# usbtin.net
KiCad netlist of a schematic drawn in EAGLE
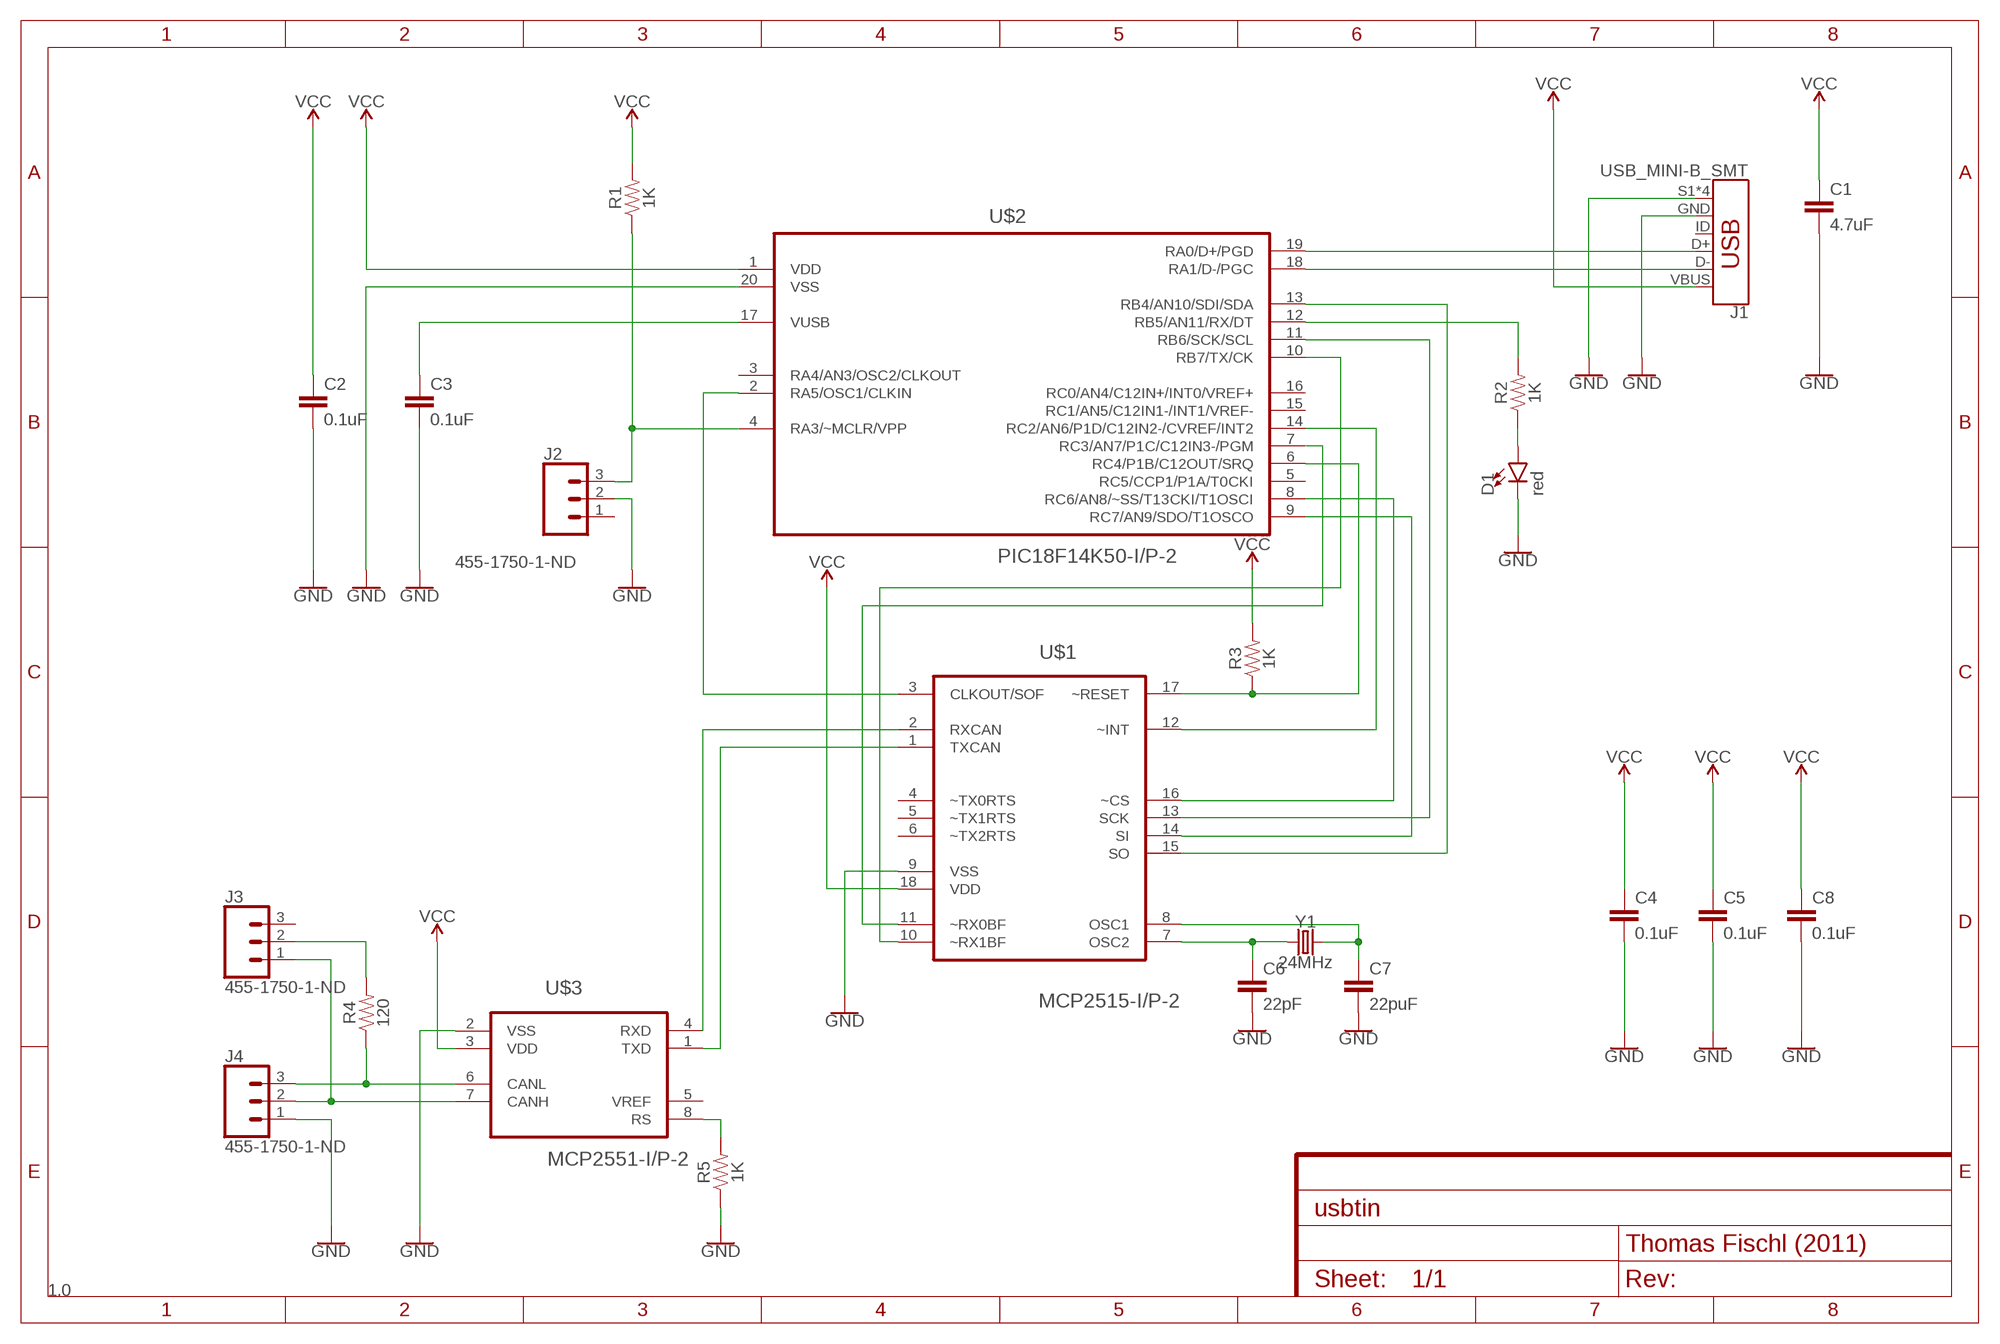
[diagram p0: schematic, sheet 1]

(export (version "E")
  (design (tool "Eeschema 10.0.6"))
  (components
    (comp (ref "C1")
      (value "4.7uF")
      (footprint "eagle-import:1206")
      (libsource (lib "eagle-import") (part "4.7UF-1206-16V-(+80/-20%)"))
    )
    (comp (ref "C2")
      (value "0.1uF")
      (footprint "eagle-import:0603")
      (libsource (lib "eagle-import") (part "0.1UF-0603-25V-5%"))
    )
    (comp (ref "C3")
      (value "0.1uF")
      (footprint "eagle-import:0603")
      (libsource (lib "eagle-import") (part "0.1UF-0603-25V-5%"))
    )
    (comp (ref "C4")
      (value "0.1uF")
      (footprint "eagle-import:0603")
      (libsource (lib "eagle-import") (part "0.1UF-0603-25V-5%"))
    )
    (comp (ref "C5")
      (value "0.1uF")
      (footprint "eagle-import:0603")
      (libsource (lib "eagle-import") (part "0.1UF-0603-25V-5%"))
    )
    (comp (ref "C6")
      (value "22pF")
      (footprint "eagle-import:0805")
      (libsource (lib "eagle-import") (part "1.0UF-0805-25V-10%"))
    )
    (comp (ref "C7")
      (value "22puF")
      (footprint "eagle-import:0805")
      (libsource (lib "eagle-import") (part "1.0UF-0805-25V-10%"))
    )
    (comp (ref "C8")
      (value "0.1uF")
      (footprint "eagle-import:0603")
      (libsource (lib "eagle-import") (part "0.1UF-0603-25V-5%"))
    )
    (comp (ref "D1")
      (value "red")
      (footprint "eagle-import:LED-1206")
      (libsource (lib "eagle-import") (part "LED1206"))
    )
    (comp (ref "J1")
      (value "USB_MINI-B_SMT")
      (footprint "eagle-import:USB-MINIB")
      (libsource (lib "eagle-import") (part "USB_MINI-B_SMT"))
    )
    (comp (ref "J2")
      (value "455-1750-1-ND")
      (footprint "eagle-import:1X03")
      (libsource (lib "eagle-import") (part "CONN_03"))
    )
    (comp (ref "J3")
      (value "455-1750-1-ND")
      (footprint "eagle-import:1X03")
      (libsource (lib "eagle-import") (part "CONN_03"))
    )
    (comp (ref "J4")
      (value "455-1750-1-ND")
      (footprint "eagle-import:1X03")
      (libsource (lib "eagle-import") (part "CONN_03"))
    )
    (comp (ref "R1")
      (value "1K")
      (footprint "eagle-import:0805")
      (libsource (lib "eagle-import") (part "0.3OHM-0805-1/8W-1%"))
    )
    (comp (ref "R2")
      (value "1K")
      (footprint "eagle-import:0805")
      (libsource (lib "eagle-import") (part "0.3OHM-0805-1/8W-1%"))
    )
    (comp (ref "R3")
      (value "1K")
      (footprint "eagle-import:0805")
      (libsource (lib "eagle-import") (part "0.3OHM-0805-1/8W-1%"))
    )
    (comp (ref "R4")
      (value "120")
      (footprint "eagle-import:0805")
      (libsource (lib "eagle-import") (part "0.3OHM-0805-1/8W-1%"))
    )
    (comp (ref "R5")
      (value "1K")
      (footprint "eagle-import:0805")
      (libsource (lib "eagle-import") (part "0.3OHM-0805-1/8W-1%"))
    )
    (comp (ref "U$1")
      (value "MCP2515-I/P-2")
      (footprint "eagle-import:DIP254P762X432-18")
      (fields (field (name "MPN") "MCP2515-I/P"))
      (libsource (lib "eagle-import") (part "MCP2515-I/P-2"))
    )
    (comp (ref "U$2")
      (value "PIC18F14K50-I/P-2")
      (footprint "eagle-import:DIP254P762X533-20")
      (fields (field (name "MPN") "PIC18F14K50-I/P"))
      (libsource (lib "eagle-import") (part "PIC18F14K50-I/P-2"))
    )
    (comp (ref "U$3")
      (value "MCP2551-I/P-2")
      (footprint "eagle-import:DIP254P762X432-8")
      (fields (field (name "MPN") "MCP2551-I/P"))
      (libsource (lib "eagle-import") (part "MCP2551-I/P-2"))
    )
    (comp (ref "Y1")
      (value "24MHz")
      (footprint "eagle-import:HC49US")
      (libsource (lib "eagle-import") (part "CRYSTALPTH-HC49US"))
    )
  )
  (nets
    (net (code "1") (name "GND") (class "Default")
      (node (ref "C1") (pin "2") (pinfunction "2_2") (pintype "passive"))
      (node (ref "C2") (pin "2") (pinfunction "2_2") (pintype "passive"))
      (node (ref "C3") (pin "2") (pinfunction "2_2") (pintype "passive"))
      (node (ref "C4") (pin "2") (pinfunction "2_2") (pintype "passive"))
      (node (ref "C5") (pin "2") (pinfunction "2_2") (pintype "passive"))
      (node (ref "C6") (pin "2") (pinfunction "2_2") (pintype "passive"))
      (node (ref "C7") (pin "2") (pinfunction "2_2") (pintype "passive"))
      (node (ref "C8") (pin "2") (pinfunction "2_2") (pintype "passive"))
      (node (ref "D1") (pin "C") (pinfunction "C_C") (pintype "passive"))
      (node (ref "J1") (pin "GND") (pinfunction "GND_GND") (pintype "power_in"))
      (node (ref "J1") (pin "S1") (pinfunction "SHIELD_S1") (pintype "bidirectional"))
      (node (ref "J1") (pin "S2") (pinfunction "SHIELD_S2") (pintype "bidirectional"))
      (node (ref "J1") (pin "S3") (pinfunction "SHIELD_S3") (pintype "bidirectional"))
      (node (ref "J1") (pin "S4") (pinfunction "SHIELD_S4") (pintype "bidirectional"))
      (node (ref "J2") (pin "2") (pinfunction "2_2") (pintype "passive"))
      (node (ref "J4") (pin "1") (pinfunction "1_1") (pintype "passive"))
      (node (ref "R5") (pin "1") (pinfunction "1_1") (pintype "passive"))
      (node (ref "U$1") (pin "9") (pinfunction "VSS_9") (pintype "power_in"))
      (node (ref "U$2") (pin "20") (pinfunction "VSS_20") (pintype "power_in"))
      (node (ref "U$3") (pin "2") (pinfunction "VSS_2") (pintype "power_in"))
    )
    (net (code "2") (name "Net-(D1-PadA)") (class "Default")
      (node (ref "D1") (pin "A") (pinfunction "A_A") (pintype "passive"))
      (node (ref "R2") (pin "1") (pinfunction "1_1") (pintype "passive"))
    )
    (net (code "3") (name "Net-(J3-Pad2)") (class "Default")
      (node (ref "J3") (pin "2") (pinfunction "2_2") (pintype "passive"))
      (node (ref "R4") (pin "2") (pinfunction "2_2") (pintype "passive"))
    )
    (net (code "4") (name "Net-(U$1-CLKOUT{slash}SOF)") (class "Default")
      (node (ref "U$1") (pin "3") (pinfunction "CLKOUT/SOF_3") (pintype "output"))
      (node (ref "U$2") (pin "2") (pinfunction "RA5/OSC1/CLKIN_2") (pintype "bidirectional"))
    )
    (net (code "5") (name "Net-(U$1-OSC1)") (class "Default")
      (node (ref "C7") (pin "1") (pinfunction "1_1") (pintype "passive"))
      (node (ref "U$1") (pin "8") (pinfunction "OSC1_8") (pintype "output"))
      (node (ref "Y1") (pin "2") (pinfunction "2_2") (pintype "passive"))
    )
    (net (code "6") (name "Net-(U$1-OSC2)") (class "Default")
      (node (ref "C6") (pin "1") (pinfunction "1_1") (pintype "passive"))
      (node (ref "U$1") (pin "7") (pinfunction "OSC2_7") (pintype "output"))
      (node (ref "Y1") (pin "1") (pinfunction "1_1") (pintype "passive"))
    )
    (net (code "7") (name "Net-(U$1-RXCAN)") (class "Default")
      (node (ref "U$1") (pin "2") (pinfunction "RXCAN_2") (pintype "input"))
      (node (ref "U$3") (pin "4") (pinfunction "RXD_4") (pintype "output"))
    )
    (net (code "8") (name "Net-(U$1-SCK)") (class "Default")
      (node (ref "U$1") (pin "13") (pinfunction "SCK_13") (pintype "input"))
      (node (ref "U$2") (pin "11") (pinfunction "RB6/SCK/SCL_11") (pintype "bidirectional"))
    )
    (net (code "9") (name "Net-(U$1-SI)") (class "Default")
      (node (ref "U$1") (pin "14") (pinfunction "SI_14") (pintype "input"))
      (node (ref "U$2") (pin "9") (pinfunction "RC7/AN9/SDO/T1OSCO_9") (pintype "bidirectional"))
    )
    (net (code "10") (name "Net-(U$1-SO)") (class "Default")
      (node (ref "U$1") (pin "15") (pinfunction "SO_15") (pintype "output"))
      (node (ref "U$2") (pin "13") (pinfunction "RB4/AN10/SDI/SDA_13") (pintype "bidirectional"))
    )
    (net (code "11") (name "Net-(U$1-TXCAN)") (class "Default")
      (node (ref "U$1") (pin "1") (pinfunction "TXCAN_1") (pintype "output"))
      (node (ref "U$3") (pin "1") (pinfunction "TXD_1") (pintype "input"))
    )
    (net (code "12") (name "Net-(U$1-~{CS})") (class "Default")
      (node (ref "U$1") (pin "16") (pinfunction "~{CS}_16") (pintype "input"))
      (node (ref "U$2") (pin "8") (pinfunction "RC6/AN8/~{SS/T13CKI/T1OSCI}_8") (pintype "bidirectional"))
    )
    (net (code "13") (name "Net-(U$1-~{INT})") (class "Default")
      (node (ref "U$1") (pin "12") (pinfunction "~{INT}_12") (pintype "output"))
      (node (ref "U$2") (pin "14") (pinfunction "RC2/AN6/P1D/C12IN2-/CVREF/INT2_14") (pintype "bidirectional"))
    )
    (net (code "14") (name "Net-(U$1-~{RESET})") (class "Default")
      (node (ref "R3") (pin "1") (pinfunction "1_1") (pintype "passive"))
      (node (ref "U$1") (pin "17") (pinfunction "~{RESET}_17") (pintype "input"))
      (node (ref "U$2") (pin "6") (pinfunction "RC4/P1B/C12OUT/SRQ_6") (pintype "bidirectional"))
    )
    (net (code "15") (name "Net-(U$1-~{RX0BF})") (class "Default")
      (node (ref "U$1") (pin "11") (pinfunction "~{RX0BF}_11") (pintype "output"))
      (node (ref "U$2") (pin "7") (pinfunction "RC3/AN7/P1C/C12IN3-/PGM_7") (pintype "bidirectional"))
    )
    (net (code "16") (name "Net-(U$1-~{RX1BF})") (class "Default")
      (node (ref "U$1") (pin "10") (pinfunction "~{RX1BF}_10") (pintype "output"))
      (node (ref "U$2") (pin "10") (pinfunction "RB7/TX/CK_10") (pintype "bidirectional"))
    )
    (net (code "17") (name "Net-(U$2-RA0{slash}D+{slash}PGD)") (class "Default")
      (node (ref "J1") (pin "D+") (pinfunction "D+_D+") (pintype "bidirectional"))
      (node (ref "U$2") (pin "19") (pinfunction "RA0/D+/PGD_19") (pintype "bidirectional"))
    )
    (net (code "18") (name "Net-(U$2-RA1{slash}D-{slash}PGC)") (class "Default")
      (node (ref "J1") (pin "D-") (pinfunction "D-_D-") (pintype "bidirectional"))
      (node (ref "U$2") (pin "18") (pinfunction "RA1/D-/PGC_18") (pintype "bidirectional"))
    )
    (net (code "19") (name "Net-(U$2-RA3{slash}~{MCLR{slash}VPP})") (class "Default")
      (node (ref "J2") (pin "3") (pinfunction "3_3") (pintype "passive"))
      (node (ref "R1") (pin "1") (pinfunction "1_1") (pintype "passive"))
      (node (ref "U$2") (pin "4") (pinfunction "RA3/~{MCLR/VPP}_4") (pintype "input"))
    )
    (net (code "20") (name "Net-(U$2-RB5{slash}AN11{slash}RX{slash}DT)") (class "Default")
      (node (ref "R2") (pin "2") (pinfunction "2_2") (pintype "passive"))
      (node (ref "U$2") (pin "12") (pinfunction "RB5/AN11/RX/DT_12") (pintype "bidirectional"))
    )
    (net (code "21") (name "Net-(U$2-VUSB)") (class "Default")
      (node (ref "C3") (pin "1") (pinfunction "1_1") (pintype "passive"))
      (node (ref "U$2") (pin "17") (pinfunction "VUSB_17") (pintype "power_in"))
    )
    (net (code "22") (name "Net-(U$3-CANH)") (class "Default")
      (node (ref "J3") (pin "1") (pinfunction "1_1") (pintype "passive"))
      (node (ref "J4") (pin "2") (pinfunction "2_2") (pintype "passive"))
      (node (ref "U$3") (pin "7") (pinfunction "CANH_7") (pintype "bidirectional"))
    )
    (net (code "23") (name "Net-(U$3-CANL)") (class "Default")
      (node (ref "J4") (pin "3") (pinfunction "3_3") (pintype "passive"))
      (node (ref "R4") (pin "1") (pinfunction "1_1") (pintype "passive"))
      (node (ref "U$3") (pin "6") (pinfunction "CANL_6") (pintype "bidirectional"))
    )
    (net (code "24") (name "Net-(U$3-RS)") (class "Default")
      (node (ref "R5") (pin "2") (pinfunction "2_2") (pintype "passive"))
      (node (ref "U$3") (pin "8") (pinfunction "RS_8") (pintype "input"))
    )
    (net (code "25") (name "VCC") (class "Default")
      (node (ref "C1") (pin "1") (pinfunction "1_1") (pintype "passive"))
      (node (ref "C2") (pin "1") (pinfunction "1_1") (pintype "passive"))
      (node (ref "C4") (pin "1") (pinfunction "1_1") (pintype "passive"))
      (node (ref "C5") (pin "1") (pinfunction "1_1") (pintype "passive"))
      (node (ref "C8") (pin "1") (pinfunction "1_1") (pintype "passive"))
      (node (ref "J1") (pin "VBUS") (pinfunction "VBUS_VBUS") (pintype "power_in"))
      (node (ref "R1") (pin "2") (pinfunction "2_2") (pintype "passive"))
      (node (ref "R3") (pin "2") (pinfunction "2_2") (pintype "passive"))
      (node (ref "U$1") (pin "18") (pinfunction "VDD_18") (pintype "power_in"))
      (node (ref "U$2") (pin "1") (pinfunction "VDD_1") (pintype "power_in"))
      (node (ref "U$3") (pin "3") (pinfunction "VDD_3") (pintype "power_in"))
    )
    (net (code "26") (name "unconnected-(J1-PadID)") (class "Default")
      (node (ref "J1") (pin "ID") (pinfunction "ID_ID") (pintype "bidirectional"))
    )
    (net (code "27") (name "unconnected-(J2-Pad1)") (class "Default")
      (node (ref "J2") (pin "1") (pinfunction "1_1") (pintype "passive"))
    )
    (net (code "28") (name "unconnected-(J3-Pad3)") (class "Default")
      (node (ref "J3") (pin "3") (pinfunction "3_3") (pintype "passive"))
    )
    (net (code "29") (name "unconnected-(U$1-~{TX0RTS}-Pad4)") (class "Default")
      (node (ref "U$1") (pin "4") (pinfunction "~{TX0RTS}_4") (pintype "input"))
    )
    (net (code "30") (name "unconnected-(U$1-~{TX1RTS}-Pad5)") (class "Default")
      (node (ref "U$1") (pin "5") (pinfunction "~{TX1RTS}_5") (pintype "input"))
    )
    (net (code "31") (name "unconnected-(U$1-~{TX2RTS}-Pad6)") (class "Default")
      (node (ref "U$1") (pin "6") (pinfunction "~{TX2RTS}_6") (pintype "input"))
    )
    (net (code "32") (name "unconnected-(U$2-RA4{slash}AN3{slash}OSC2{slash}CLKOUT-Pad3)") (class "Default")
      (node (ref "U$2") (pin "3") (pinfunction "RA4/AN3/OSC2/CLKOUT_3") (pintype "bidirectional"))
    )
    (net (code "33") (name "unconnected-(U$2-RC0{slash}AN4{slash}C12IN+{slash}INT0{slash}VREF+-Pad16)") (class "Default")
      (node (ref "U$2") (pin "16") (pinfunction "RC0/AN4/C12IN+/INT0/VREF+_16") (pintype "bidirectional"))
    )
    (net (code "34") (name "unconnected-(U$2-RC1{slash}AN5{slash}C12IN1-{slash}INT1{slash}VREF--Pad15)") (class "Default")
      (node (ref "U$2") (pin "15") (pinfunction "RC1/AN5/C12IN1-/INT1/VREF-_15") (pintype "bidirectional"))
    )
    (net (code "35") (name "unconnected-(U$2-RC5{slash}CCP1{slash}P1A{slash}T0CKI-Pad5)") (class "Default")
      (node (ref "U$2") (pin "5") (pinfunction "RC5/CCP1/P1A/T0CKI_5") (pintype "bidirectional"))
    )
    (net (code "36") (name "unconnected-(U$3-VREF-Pad5)") (class "Default")
      (node (ref "U$3") (pin "5") (pinfunction "VREF_5") (pintype "output"))
    )
  )
)
